# BBB_Breakout_Cape_0.net
KiCad netlist of a schematic drawn in EAGLE
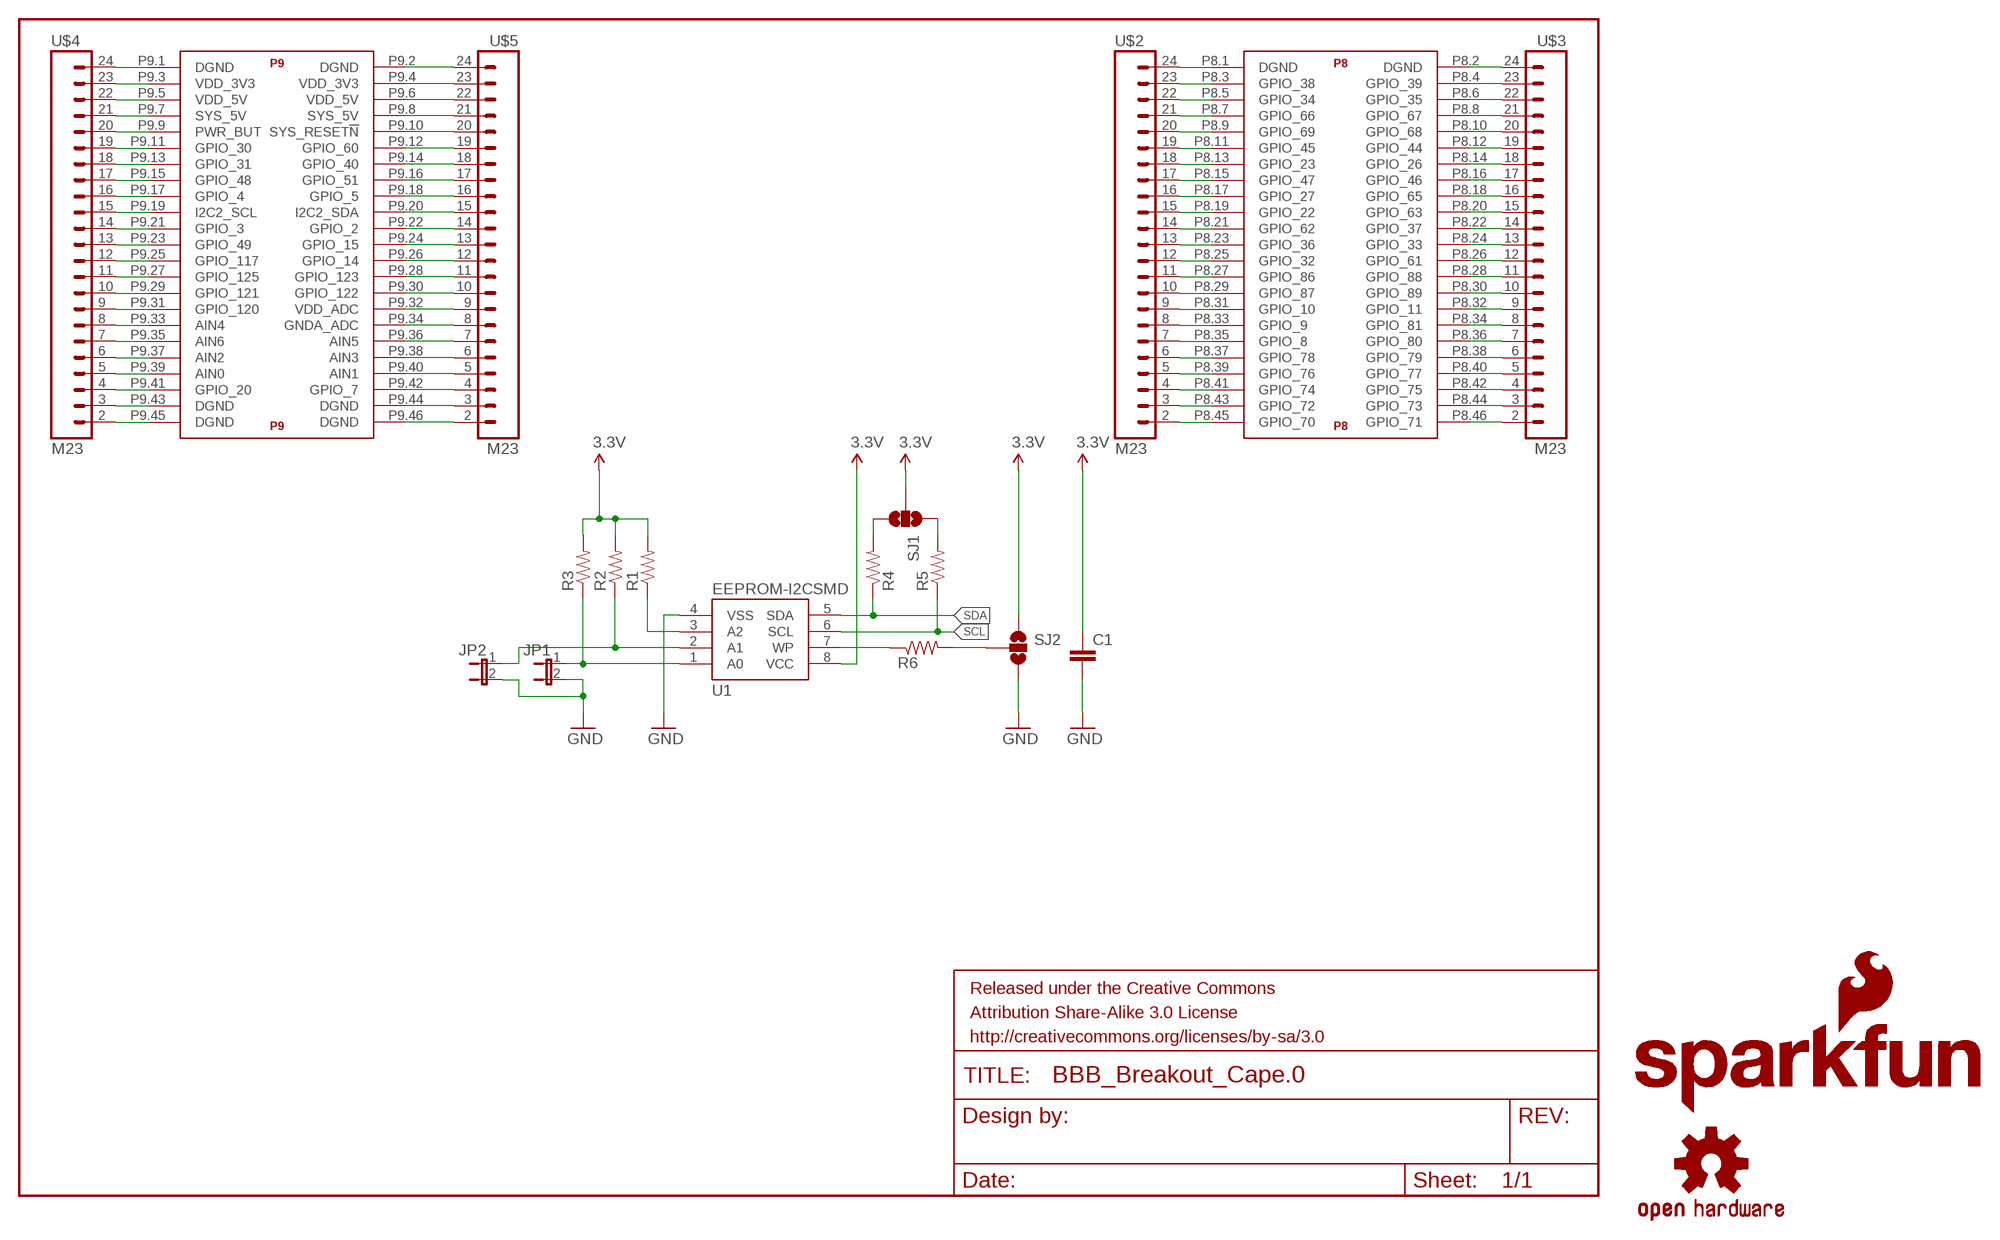
[diagram p0: schematic, sheet 1]

(export (version "E")
  (design (tool "Eeschema 10.0.6"))
  (components
    (comp (ref "C1")
      (value "0.1UF-25V(+80/-20%)(0603)")
      (footprint "eagle-import:0603-CAP")
      (libsource (lib "eagle-import") (part "0.1UF-25V(+80/-20%)(0603)"))
    )
    (comp (ref "FRAME1")
      (value "FRAME-LETTER")
      (footprint "eagle-import:CREATIVE_COMMONS")
      (libsource (lib "eagle-import") (part "FRAME-LETTER"))
    )
    (comp (ref "JP1")
      (value "JUMPER-2SMD-NO")
      (footprint "eagle-import:SJ_2S-NO")
      (libsource (lib "eagle-import") (part "JUMPER-2SMD-NO"))
    )
    (comp (ref "JP2")
      (value "JUMPER-2SMD-NO")
      (footprint "eagle-import:SJ_2S-NO")
      (libsource (lib "eagle-import") (part "JUMPER-2SMD-NO"))
    )
    (comp (ref "LOGO2")
      (value "OSHW-LOGOS")
      (footprint "eagle-import:OSHW-LOGO-S")
      (libsource (lib "eagle-import") (part "OSHW-LOGOS"))
    )
    (comp (ref "LOGO3")
      (value "SFE_LOGO_NAME_FLAME.1_INCH")
      (footprint "eagle-import:SFE_LOGO_NAME_FLAME_.1")
      (libsource (lib "eagle-import") (part "SFE_LOGO_NAME_FLAME.1_INCH"))
    )
    (comp (ref "R1")
      (value "4.7KOHM1/10W1%(0603)")
      (footprint "eagle-import:0603")
      (libsource (lib "eagle-import") (part "4.7KOHM1/10W1%(0603)"))
    )
    (comp (ref "R2")
      (value "4.7KOHM1/10W1%(0603)")
      (footprint "eagle-import:0603")
      (libsource (lib "eagle-import") (part "4.7KOHM1/10W1%(0603)"))
    )
    (comp (ref "R3")
      (value "4.7KOHM1/10W1%(0603)")
      (footprint "eagle-import:0603")
      (libsource (lib "eagle-import") (part "4.7KOHM1/10W1%(0603)"))
    )
    (comp (ref "R4")
      (value "4.7KOHM1/10W1%(0603)")
      (footprint "eagle-import:0603")
      (fields (field (name "PROD_ID") "RES-07857"))
      (libsource (lib "eagle-import") (part "4.7KOHM1/10W1%(0603)"))
    )
    (comp (ref "R5")
      (value "4.7KOHM1/10W1%(0603)")
      (footprint "eagle-import:0603")
      (fields (field (name "PROD_ID") "RES-07857"))
      (libsource (lib "eagle-import") (part "4.7KOHM1/10W1%(0603)"))
    )
    (comp (ref "R6")
      (value "10KOHM1/10W1%(0603)0603")
      (footprint "eagle-import:0603-RES")
      (libsource (lib "eagle-import") (part "10KOHM1/10W1%(0603)0603"))
    )
    (comp (ref "SJ1")
      (value "SOLDERJUMPER_2WAYPASTE1&2&3")
      (footprint "eagle-import:SJ_3_PASTE1&2&3")
      (libsource (lib "eagle-import") (part "SOLDERJUMPER_2WAYPASTE1&2&3"))
    )
    (comp (ref "SJ2")
      (value "SOLDERJUMPER_2WAYPASTE2&3")
      (footprint "eagle-import:SJ_3_PASTE2&3")
      (libsource (lib "eagle-import") (part "SOLDERJUMPER_2WAYPASTE2&3"))
    )
    (comp (ref "U$1")
      (value "BEAGLE_BONE_BLACK_CAPE")
      (footprint "eagle-import:BEAGLE_BONE_BLACK_CAPE")
      (libsource (lib "eagle-import") (part "BEAGLE_BONE_BLACK_CAPE"))
    )
    (comp (ref "U$2")
      (value "M23")
      (footprint "eagle-import:1X23")
      (libsource (lib "eagle-import") (part "M23"))
    )
    (comp (ref "U$3")
      (value "M23")
      (footprint "eagle-import:1X23")
      (libsource (lib "eagle-import") (part "M23"))
    )
    (comp (ref "U$4")
      (value "M23")
      (footprint "eagle-import:1X23")
      (libsource (lib "eagle-import") (part "M23"))
    )
    (comp (ref "U$5")
      (value "M23")
      (footprint "eagle-import:1X23")
      (libsource (lib "eagle-import") (part "M23"))
    )
    (comp (ref "U1")
      (value "EEPROM-I2CSMD")
      (footprint "eagle-import:SO08")
      (libsource (lib "eagle-import") (part "EEPROM-I2CSMD"))
    )
  )
  (nets
    (net (code "1") (name "3.3V") (class "Default")
      (node (ref "C1") (pin "1") (pinfunction "1_1") (pintype "passive"))
      (node (ref "R1") (pin "2") (pinfunction "2_2") (pintype "passive"))
      (node (ref "R2") (pin "2") (pinfunction "2_2") (pintype "passive"))
      (node (ref "R3") (pin "2") (pinfunction "2_2") (pintype "passive"))
      (node (ref "SJ1") (pin "2") (pinfunction "2_2") (pintype "passive"))
      (node (ref "SJ2") (pin "1") (pinfunction "1_1") (pintype "passive"))
      (node (ref "U1") (pin "8") (pinfunction "VCC_8") (pintype "power_in"))
    )
    (net (code "2") (name "GND") (class "Default")
      (node (ref "C1") (pin "2") (pinfunction "2_2") (pintype "passive"))
      (node (ref "JP1") (pin "2") (pinfunction "2_2") (pintype "passive"))
      (node (ref "JP2") (pin "2") (pinfunction "2_2") (pintype "passive"))
      (node (ref "SJ2") (pin "3") (pinfunction "3_3") (pintype "passive"))
      (node (ref "U1") (pin "4") (pinfunction "VSS_4") (pintype "power_in"))
    )
    (net (code "3") (name "Net-(R4-Pad2)") (class "Default")
      (node (ref "R4") (pin "2") (pinfunction "2_2") (pintype "passive"))
      (node (ref "SJ1") (pin "3") (pinfunction "3_3") (pintype "passive"))
    )
    (net (code "4") (name "Net-(R5-Pad2)") (class "Default")
      (node (ref "R5") (pin "2") (pinfunction "2_2") (pintype "passive"))
      (node (ref "SJ1") (pin "1") (pinfunction "1_1") (pintype "passive"))
    )
    (net (code "5") (name "Net-(R6-Pad2)") (class "Default")
      (node (ref "R6") (pin "2") (pinfunction "2_2") (pintype "passive"))
      (node (ref "SJ2") (pin "2") (pinfunction "2_2") (pintype "passive"))
    )
    (net (code "6") (name "Net-(U$1A-DGND-PadP8.1)") (class "Default")
      (node (ref "U$1") (pin "P8.1") (pinfunction "DGND_P8.1") (pintype "bidirectional"))
      (node (ref "U$2") (pin "24") (pinfunction "24_24") (pintype "passive"))
    )
    (net (code "7") (name "Net-(U$1A-DGND-PadP8.2)") (class "Default")
      (node (ref "U$1") (pin "P8.2") (pinfunction "DGND_P8.2") (pintype "bidirectional"))
      (node (ref "U$3") (pin "24") (pinfunction "24_24") (pintype "passive"))
    )
    (net (code "8") (name "Net-(U$1A-GPIO_8)") (class "Default")
      (node (ref "U$1") (pin "P8.35") (pinfunction "GPIO_8_P8.35") (pintype "bidirectional"))
      (node (ref "U$2") (pin "7") (pinfunction "7_7") (pintype "passive"))
    )
    (net (code "9") (name "Net-(U$1A-GPIO_9)") (class "Default")
      (node (ref "U$1") (pin "P8.33") (pinfunction "GPIO_9_P8.33") (pintype "bidirectional"))
      (node (ref "U$2") (pin "8") (pinfunction "8_8") (pintype "passive"))
    )
    (net (code "10") (name "Net-(U$1A-GPIO_10)") (class "Default")
      (node (ref "U$1") (pin "P8.31") (pinfunction "GPIO_10_P8.31") (pintype "bidirectional"))
      (node (ref "U$2") (pin "9") (pinfunction "9_9") (pintype "passive"))
    )
    (net (code "11") (name "Net-(U$1A-GPIO_11)") (class "Default")
      (node (ref "U$1") (pin "P8.32") (pinfunction "GPIO_11_P8.32") (pintype "bidirectional"))
      (node (ref "U$3") (pin "9") (pinfunction "9_9") (pintype "passive"))
    )
    (net (code "12") (name "Net-(U$1A-GPIO_22)") (class "Default")
      (node (ref "U$1") (pin "P8.19") (pinfunction "GPIO_22_P8.19") (pintype "bidirectional"))
      (node (ref "U$2") (pin "15") (pinfunction "15_15") (pintype "passive"))
    )
    (net (code "13") (name "Net-(U$1A-GPIO_23)") (class "Default")
      (node (ref "U$1") (pin "P8.13") (pinfunction "GPIO_23_P8.13") (pintype "bidirectional"))
      (node (ref "U$2") (pin "18") (pinfunction "18_18") (pintype "passive"))
    )
    (net (code "14") (name "Net-(U$1A-GPIO_26)") (class "Default")
      (node (ref "U$1") (pin "P8.14") (pinfunction "GPIO_26_P8.14") (pintype "bidirectional"))
      (node (ref "U$3") (pin "18") (pinfunction "18_18") (pintype "passive"))
    )
    (net (code "15") (name "Net-(U$1A-GPIO_27)") (class "Default")
      (node (ref "U$1") (pin "P8.17") (pinfunction "GPIO_27_P8.17") (pintype "bidirectional"))
      (node (ref "U$2") (pin "16") (pinfunction "16_16") (pintype "passive"))
    )
    (net (code "16") (name "Net-(U$1A-GPIO_32)") (class "Default")
      (node (ref "U$1") (pin "P8.25") (pinfunction "GPIO_32_P8.25") (pintype "bidirectional"))
      (node (ref "U$2") (pin "12") (pinfunction "12_12") (pintype "passive"))
    )
    (net (code "17") (name "Net-(U$1A-GPIO_33)") (class "Default")
      (node (ref "U$1") (pin "P8.24") (pinfunction "GPIO_33_P8.24") (pintype "bidirectional"))
      (node (ref "U$3") (pin "13") (pinfunction "13_13") (pintype "passive"))
    )
    (net (code "18") (name "Net-(U$1A-GPIO_34)") (class "Default")
      (node (ref "U$1") (pin "P8.5") (pinfunction "GPIO_34_P8.5") (pintype "bidirectional"))
      (node (ref "U$2") (pin "22") (pinfunction "22_22") (pintype "passive"))
    )
    (net (code "19") (name "Net-(U$1A-GPIO_35)") (class "Default")
      (node (ref "U$1") (pin "P8.6") (pinfunction "GPIO_35_P8.6") (pintype "bidirectional"))
      (node (ref "U$3") (pin "22") (pinfunction "22_22") (pintype "passive"))
    )
    (net (code "20") (name "Net-(U$1A-GPIO_36)") (class "Default")
      (node (ref "U$1") (pin "P8.23") (pinfunction "GPIO_36_P8.23") (pintype "bidirectional"))
      (node (ref "U$2") (pin "13") (pinfunction "13_13") (pintype "passive"))
    )
    (net (code "21") (name "Net-(U$1A-GPIO_37)") (class "Default")
      (node (ref "U$1") (pin "P8.22") (pinfunction "GPIO_37_P8.22") (pintype "bidirectional"))
      (node (ref "U$3") (pin "14") (pinfunction "14_14") (pintype "passive"))
    )
    (net (code "22") (name "Net-(U$1A-GPIO_38)") (class "Default")
      (node (ref "U$1") (pin "P8.3") (pinfunction "GPIO_38_P8.3") (pintype "bidirectional"))
      (node (ref "U$2") (pin "23") (pinfunction "23_23") (pintype "passive"))
    )
    (net (code "23") (name "Net-(U$1A-GPIO_39)") (class "Default")
      (node (ref "U$1") (pin "P8.4") (pinfunction "GPIO_39_P8.4") (pintype "bidirectional"))
      (node (ref "U$3") (pin "23") (pinfunction "23_23") (pintype "passive"))
    )
    (net (code "24") (name "Net-(U$1A-GPIO_44)") (class "Default")
      (node (ref "U$1") (pin "P8.12") (pinfunction "GPIO_44_P8.12") (pintype "bidirectional"))
      (node (ref "U$3") (pin "19") (pinfunction "19_19") (pintype "passive"))
    )
    (net (code "25") (name "Net-(U$1A-GPIO_45)") (class "Default")
      (node (ref "U$1") (pin "P8.11") (pinfunction "GPIO_45_P8.11") (pintype "bidirectional"))
      (node (ref "U$2") (pin "19") (pinfunction "19_19") (pintype "passive"))
    )
    (net (code "26") (name "Net-(U$1A-GPIO_46)") (class "Default")
      (node (ref "U$1") (pin "P8.16") (pinfunction "GPIO_46_P8.16") (pintype "bidirectional"))
      (node (ref "U$3") (pin "17") (pinfunction "17_17") (pintype "passive"))
    )
    (net (code "27") (name "Net-(U$1A-GPIO_47)") (class "Default")
      (node (ref "U$1") (pin "P8.15") (pinfunction "GPIO_47_P8.15") (pintype "bidirectional"))
      (node (ref "U$2") (pin "17") (pinfunction "17_17") (pintype "passive"))
    )
    (net (code "28") (name "Net-(U$1A-GPIO_61)") (class "Default")
      (node (ref "U$1") (pin "P8.26") (pinfunction "GPIO_61_P8.26") (pintype "bidirectional"))
      (node (ref "U$3") (pin "12") (pinfunction "12_12") (pintype "passive"))
    )
    (net (code "29") (name "Net-(U$1A-GPIO_62)") (class "Default")
      (node (ref "U$1") (pin "P8.21") (pinfunction "GPIO_62_P8.21") (pintype "bidirectional"))
      (node (ref "U$2") (pin "14") (pinfunction "14_14") (pintype "passive"))
    )
    (net (code "30") (name "Net-(U$1A-GPIO_63)") (class "Default")
      (node (ref "U$1") (pin "P8.20") (pinfunction "GPIO_63_P8.20") (pintype "bidirectional"))
      (node (ref "U$3") (pin "15") (pinfunction "15_15") (pintype "passive"))
    )
    (net (code "31") (name "Net-(U$1A-GPIO_65)") (class "Default")
      (node (ref "U$1") (pin "P8.18") (pinfunction "GPIO_65_P8.18") (pintype "bidirectional"))
      (node (ref "U$3") (pin "16") (pinfunction "16_16") (pintype "passive"))
    )
    (net (code "32") (name "Net-(U$1A-GPIO_66)") (class "Default")
      (node (ref "U$1") (pin "P8.7") (pinfunction "GPIO_66_P8.7") (pintype "bidirectional"))
      (node (ref "U$2") (pin "21") (pinfunction "21_21") (pintype "passive"))
    )
    (net (code "33") (name "Net-(U$1A-GPIO_67)") (class "Default")
      (node (ref "U$1") (pin "P8.8") (pinfunction "GPIO_67_P8.8") (pintype "bidirectional"))
      (node (ref "U$3") (pin "21") (pinfunction "21_21") (pintype "passive"))
    )
    (net (code "34") (name "Net-(U$1A-GPIO_68)") (class "Default")
      (node (ref "U$1") (pin "P8.10") (pinfunction "GPIO_68_P8.10") (pintype "bidirectional"))
      (node (ref "U$3") (pin "20") (pinfunction "20_20") (pintype "passive"))
    )
    (net (code "35") (name "Net-(U$1A-GPIO_69)") (class "Default")
      (node (ref "U$1") (pin "P8.9") (pinfunction "GPIO_69_P8.9") (pintype "bidirectional"))
      (node (ref "U$2") (pin "20") (pinfunction "20_20") (pintype "passive"))
    )
    (net (code "36") (name "Net-(U$1A-GPIO_70)") (class "Default")
      (node (ref "U$1") (pin "P8.45") (pinfunction "GPIO_70_P8.45") (pintype "bidirectional"))
      (node (ref "U$2") (pin "2") (pinfunction "2_2") (pintype "passive"))
    )
    (net (code "37") (name "Net-(U$1A-GPIO_71)") (class "Default")
      (node (ref "U$1") (pin "P8.46") (pinfunction "GPIO_71_P8.46") (pintype "bidirectional"))
      (node (ref "U$3") (pin "2") (pinfunction "2_2") (pintype "passive"))
    )
    (net (code "38") (name "Net-(U$1A-GPIO_72)") (class "Default")
      (node (ref "U$1") (pin "P8.43") (pinfunction "GPIO_72_P8.43") (pintype "bidirectional"))
      (node (ref "U$2") (pin "3") (pinfunction "3_3") (pintype "passive"))
    )
    (net (code "39") (name "Net-(U$1A-GPIO_73)") (class "Default")
      (node (ref "U$1") (pin "P8.44") (pinfunction "GPIO_73_P8.44") (pintype "bidirectional"))
      (node (ref "U$3") (pin "3") (pinfunction "3_3") (pintype "passive"))
    )
    (net (code "40") (name "Net-(U$1A-GPIO_74)") (class "Default")
      (node (ref "U$1") (pin "P8.41") (pinfunction "GPIO_74_P8.41") (pintype "bidirectional"))
      (node (ref "U$2") (pin "4") (pinfunction "4_4") (pintype "passive"))
    )
    (net (code "41") (name "Net-(U$1A-GPIO_75)") (class "Default")
      (node (ref "U$1") (pin "P8.42") (pinfunction "GPIO_75_P8.42") (pintype "bidirectional"))
      (node (ref "U$3") (pin "4") (pinfunction "4_4") (pintype "passive"))
    )
    (net (code "42") (name "Net-(U$1A-GPIO_76)") (class "Default")
      (node (ref "U$1") (pin "P8.39") (pinfunction "GPIO_76_P8.39") (pintype "bidirectional"))
      (node (ref "U$2") (pin "5") (pinfunction "5_5") (pintype "passive"))
    )
    (net (code "43") (name "Net-(U$1A-GPIO_77)") (class "Default")
      (node (ref "U$1") (pin "P8.40") (pinfunction "GPIO_77_P8.40") (pintype "bidirectional"))
      (node (ref "U$3") (pin "5") (pinfunction "5_5") (pintype "passive"))
    )
    (net (code "44") (name "Net-(U$1A-GPIO_78)") (class "Default")
      (node (ref "U$1") (pin "P8.37") (pinfunction "GPIO_78_P8.37") (pintype "bidirectional"))
      (node (ref "U$2") (pin "6") (pinfunction "6_6") (pintype "passive"))
    )
    (net (code "45") (name "Net-(U$1A-GPIO_79)") (class "Default")
      (node (ref "U$1") (pin "P8.38") (pinfunction "GPIO_79_P8.38") (pintype "bidirectional"))
      (node (ref "U$3") (pin "6") (pinfunction "6_6") (pintype "passive"))
    )
    (net (code "46") (name "Net-(U$1A-GPIO_80)") (class "Default")
      (node (ref "U$1") (pin "P8.36") (pinfunction "GPIO_80_P8.36") (pintype "bidirectional"))
      (node (ref "U$3") (pin "7") (pinfunction "7_7") (pintype "passive"))
    )
    (net (code "47") (name "Net-(U$1A-GPIO_81)") (class "Default")
      (node (ref "U$1") (pin "P8.34") (pinfunction "GPIO_81_P8.34") (pintype "bidirectional"))
      (node (ref "U$3") (pin "8") (pinfunction "8_8") (pintype "passive"))
    )
    (net (code "48") (name "Net-(U$1A-GPIO_86)") (class "Default")
      (node (ref "U$1") (pin "P8.27") (pinfunction "GPIO_86_P8.27") (pintype "bidirectional"))
      (node (ref "U$2") (pin "11") (pinfunction "11_11") (pintype "passive"))
    )
    (net (code "49") (name "Net-(U$1A-GPIO_87)") (class "Default")
      (node (ref "U$1") (pin "P8.29") (pinfunction "GPIO_87_P8.29") (pintype "bidirectional"))
      (node (ref "U$2") (pin "10") (pinfunction "10_10") (pintype "passive"))
    )
    (net (code "50") (name "Net-(U$1A-GPIO_88)") (class "Default")
      (node (ref "U$1") (pin "P8.28") (pinfunction "GPIO_88_P8.28") (pintype "bidirectional"))
      (node (ref "U$3") (pin "11") (pinfunction "11_11") (pintype "passive"))
    )
    (net (code "51") (name "Net-(U$1A-GPIO_89)") (class "Default")
      (node (ref "U$1") (pin "P8.30") (pinfunction "GPIO_89_P8.30") (pintype "bidirectional"))
      (node (ref "U$3") (pin "10") (pinfunction "10_10") (pintype "passive"))
    )
    (net (code "52") (name "Net-(U$1B-AIN0)") (class "Default")
      (node (ref "U$1") (pin "P9.39") (pinfunction "AIN0_P9.39") (pintype "bidirectional"))
      (node (ref "U$4") (pin "5") (pinfunction "5_5") (pintype "passive"))
    )
    (net (code "53") (name "Net-(U$1B-AIN1)") (class "Default")
      (node (ref "U$1") (pin "P9.40") (pinfunction "AIN1_P9.40") (pintype "bidirectional"))
      (node (ref "U$5") (pin "5") (pinfunction "5_5") (pintype "passive"))
    )
    (net (code "54") (name "Net-(U$1B-AIN2)") (class "Default")
      (node (ref "U$1") (pin "P9.37") (pinfunction "AIN2_P9.37") (pintype "bidirectional"))
      (node (ref "U$4") (pin "6") (pinfunction "6_6") (pintype "passive"))
    )
    (net (code "55") (name "Net-(U$1B-AIN3)") (class "Default")
      (node (ref "U$1") (pin "P9.38") (pinfunction "AIN3_P9.38") (pintype "bidirectional"))
      (node (ref "U$5") (pin "6") (pinfunction "6_6") (pintype "passive"))
    )
    (net (code "56") (name "Net-(U$1B-AIN4)") (class "Default")
      (node (ref "U$1") (pin "P9.33") (pinfunction "AIN4_P9.33") (pintype "bidirectional"))
      (node (ref "U$4") (pin "8") (pinfunction "8_8") (pintype "passive"))
    )
    (net (code "57") (name "Net-(U$1B-AIN5)") (class "Default")
      (node (ref "U$1") (pin "P9.36") (pinfunction "AIN5_P9.36") (pintype "bidirectional"))
      (node (ref "U$5") (pin "7") (pinfunction "7_7") (pintype "passive"))
    )
    (net (code "58") (name "Net-(U$1B-AIN6)") (class "Default")
      (node (ref "U$1") (pin "P9.35") (pinfunction "AIN6_P9.35") (pintype "bidirectional"))
      (node (ref "U$4") (pin "7") (pinfunction "7_7") (pintype "passive"))
    )
    (net (code "59") (name "Net-(U$1B-DGND-PadP9.1)") (class "Default")
      (node (ref "U$1") (pin "P9.1") (pinfunction "DGND_P9.1") (pintype "bidirectional"))
      (node (ref "U$4") (pin "24") (pinfunction "24_24") (pintype "passive"))
    )
    (net (code "60") (name "Net-(U$1B-DGND-PadP9.2)") (class "Default")
      (node (ref "U$1") (pin "P9.2") (pinfunction "DGND_P9.2") (pintype "bidirectional"))
      (node (ref "U$5") (pin "24") (pinfunction "24_24") (pintype "passive"))
    )
    (net (code "61") (name "Net-(U$1B-DGND-PadP9.43)") (class "Default")
      (node (ref "U$1") (pin "P9.43") (pinfunction "DGND_P9.43") (pintype "bidirectional"))
      (node (ref "U$4") (pin "3") (pinfunction "3_3") (pintype "passive"))
    )
    (net (code "62") (name "Net-(U$1B-DGND-PadP9.44)") (class "Default")
      (node (ref "U$1") (pin "P9.44") (pinfunction "DGND_P9.44") (pintype "bidirectional"))
      (node (ref "U$5") (pin "3") (pinfunction "3_3") (pintype "passive"))
    )
    (net (code "63") (name "Net-(U$1B-DGND-PadP9.45)") (class "Default")
      (node (ref "U$1") (pin "P9.45") (pinfunction "DGND_P9.45") (pintype "bidirectional"))
      (node (ref "U$4") (pin "2") (pinfunction "2_2") (pintype "passive"))
    )
    (net (code "64") (name "Net-(U$1B-DGND-PadP9.46)") (class "Default")
      (node (ref "U$1") (pin "P9.46") (pinfunction "DGND_P9.46") (pintype "bidirectional"))
      (node (ref "U$5") (pin "2") (pinfunction "2_2") (pintype "passive"))
    )
    (net (code "65") (name "Net-(U$1B-GNDA_ADC)") (class "Default")
      (node (ref "U$1") (pin "P9.34") (pinfunction "GNDA_ADC_P9.34") (pintype "bidirectional"))
      (node (ref "U$5") (pin "8") (pinfunction "8_8") (pintype "passive"))
    )
    (net (code "66") (name "Net-(U$1B-GPIO_2)") (class "Default")
      (node (ref "U$1") (pin "P9.22") (pinfunction "GPIO_2_P9.22") (pintype "bidirectional"))
      (node (ref "U$5") (pin "14") (pinfunction "14_14") (pintype "passive"))
    )
    (net (code "67") (name "Net-(U$1B-GPIO_3)") (class "Default")
      (node (ref "U$1") (pin "P9.21") (pinfunction "GPIO_3_P9.21") (pintype "bidirectional"))
      (node (ref "U$4") (pin "14") (pinfunction "14_14") (pintype "passive"))
    )
    (net (code "68") (name "Net-(U$1B-GPIO_4)") (class "Default")
      (node (ref "U$1") (pin "P9.17") (pinfunction "GPIO_4_P9.17") (pintype "bidirectional"))
      (node (ref "U$4") (pin "16") (pinfunction "16_16") (pintype "passive"))
    )
    (net (code "69") (name "Net-(U$1B-GPIO_5)") (class "Default")
      (node (ref "U$1") (pin "P9.18") (pinfunction "GPIO_5_P9.18") (pintype "bidirectional"))
      (node (ref "U$5") (pin "16") (pinfunction "16_16") (pintype "passive"))
    )
    (net (code "70") (name "Net-(U$1B-GPIO_7)") (class "Default")
      (node (ref "U$1") (pin "P9.42") (pinfunction "GPIO_7_P9.42") (pintype "bidirectional"))
      (node (ref "U$5") (pin "4") (pinfunction "4_4") (pintype "passive"))
    )
    (net (code "71") (name "Net-(U$1B-GPIO_14)") (class "Default")
      (node (ref "U$1") (pin "P9.26") (pinfunction "GPIO_14_P9.26") (pintype "bidirectional"))
      (node (ref "U$5") (pin "12") (pinfunction "12_12") (pintype "passive"))
    )
    (net (code "72") (name "Net-(U$1B-GPIO_15)") (class "Default")
      (node (ref "U$1") (pin "P9.24") (pinfunction "GPIO_15_P9.24") (pintype "bidirectional"))
      (node (ref "U$5") (pin "13") (pinfunction "13_13") (pintype "passive"))
    )
    (net (code "73") (name "Net-(U$1B-GPIO_20)") (class "Default")
      (node (ref "U$1") (pin "P9.41") (pinfunction "GPIO_20_P9.41") (pintype "bidirectional"))
      (node (ref "U$4") (pin "4") (pinfunction "4_4") (pintype "passive"))
    )
    (net (code "74") (name "Net-(U$1B-GPIO_30)") (class "Default")
      (node (ref "U$1") (pin "P9.11") (pinfunction "GPIO_30_P9.11") (pintype "bidirectional"))
      (node (ref "U$4") (pin "19") (pinfunction "19_19") (pintype "passive"))
    )
    (net (code "75") (name "Net-(U$1B-GPIO_31)") (class "Default")
      (node (ref "U$1") (pin "P9.13") (pinfunction "GPIO_31_P9.13") (pintype "bidirectional"))
      (node (ref "U$4") (pin "18") (pinfunction "18_18") (pintype "passive"))
    )
    (net (code "76") (name "Net-(U$1B-GPIO_40)") (class "Default")
      (node (ref "U$1") (pin "P9.14") (pinfunction "GPIO_40_P9.14") (pintype "bidirectional"))
      (node (ref "U$5") (pin "18") (pinfunction "18_18") (pintype "passive"))
    )
    (net (code "77") (name "Net-(U$1B-GPIO_48)") (class "Default")
      (node (ref "U$1") (pin "P9.15") (pinfunction "GPIO_48_P9.15") (pintype "bidirectional"))
      (node (ref "U$4") (pin "17") (pinfunction "17_17") (pintype "passive"))
    )
    (net (code "78") (name "Net-(U$1B-GPIO_49)") (class "Default")
      (node (ref "U$1") (pin "P9.23") (pinfunction "GPIO_49_P9.23") (pintype "bidirectional"))
      (node (ref "U$4") (pin "13") (pinfunction "13_13") (pintype "passive"))
    )
    (net (code "79") (name "Net-(U$1B-GPIO_51)") (class "Default")
      (node (ref "U$1") (pin "P9.16") (pinfunction "GPIO_51_P9.16") (pintype "bidirectional"))
      (node (ref "U$5") (pin "17") (pinfunction "17_17") (pintype "passive"))
    )
    (net (code "80") (name "Net-(U$1B-GPIO_60)") (class "Default")
      (node (ref "U$1") (pin "P9.12") (pinfunction "GPIO_60_P9.12") (pintype "bidirectional"))
      (node (ref "U$5") (pin "19") (pinfunction "19_19") (pintype "passive"))
    )
    (net (code "81") (name "Net-(U$1B-GPIO_117)") (class "Default")
      (node (ref "U$1") (pin "P9.25") (pinfunction "GPIO_117_P9.25") (pintype "bidirectional"))
      (node (ref "U$4") (pin "12") (pinfunction "12_12") (pintype "passive"))
    )
    (net (code "82") (name "Net-(U$1B-GPIO_120)") (class "Default")
      (node (ref "U$1") (pin "P9.31") (pinfunction "GPIO_120_P9.31") (pintype "bidirectional"))
      (node (ref "U$4") (pin "9") (pinfunction "9_9") (pintype "passive"))
    )
    (net (code "83") (name "Net-(U$1B-GPIO_121)") (class "Default")
      (node (ref "U$1") (pin "P9.29") (pinfunction "GPIO_121_P9.29") (pintype "bidirectional"))
      (node (ref "U$4") (pin "10") (pinfunction "10_10") (pintype "passive"))
    )
    (net (code "84") (name "Net-(U$1B-GPIO_122)") (class "Default")
      (node (ref "U$1") (pin "P9.30") (pinfunction "GPIO_122_P9.30") (pintype "bidirectional"))
      (node (ref "U$5") (pin "10") (pinfunction "10_10") (pintype "passive"))
    )
    (net (code "85") (name "Net-(U$1B-GPIO_123)") (class "Default")
      (node (ref "U$1") (pin "P9.28") (pinfunction "GPIO_123_P9.28") (pintype "bidirectional"))
      (node (ref "U$5") (pin "11") (pinfunction "11_11") (pintype "passive"))
    )
    (net (code "86") (name "Net-(U$1B-GPIO_125)") (class "Default")
      (node (ref "U$1") (pin "P9.27") (pinfunction "GPIO_125_P9.27") (pintype "bidirectional"))
      (node (ref "U$4") (pin "11") (pinfunction "11_11") (pintype "passive"))
    )
    (net (code "87") (name "Net-(U$1B-I2C2_SCL)") (class "Default")
      (node (ref "U$1") (pin "P9.19") (pinfunction "I2C2_SCL_P9.19") (pintype "bidirectional"))
      (node (ref "U$4") (pin "15") (pinfunction "15_15") (pintype "passive"))
    )
    (net (code "88") (name "Net-(U$1B-I2C2_SDA)") (class "Default")
      (node (ref "U$1") (pin "P9.20") (pinfunction "I2C2_SDA_P9.20") (pintype "bidirectional"))
      (node (ref "U$5") (pin "15") (pinfunction "15_15") (pintype "passive"))
    )
    (net (code "89") (name "Net-(U$1B-PWR_BUT)") (class "Default")
      (node (ref "U$1") (pin "P9.9") (pinfunction "PWR_BUT_P9.9") (pintype "bidirectional"))
      (node (ref "U$4") (pin "20") (pinfunction "20_20") (pintype "passive"))
    )
    (net (code "90") (name "Net-(U$1B-SYS_5V-PadP9.7)") (class "Default")
      (node (ref "U$1") (pin "P9.7") (pinfunction "SYS_5V_P9.7") (pintype "bidirectional"))
      (node (ref "U$4") (pin "21") (pinfunction "21_21") (pintype "passive"))
    )
    (net (code "91") (name "Net-(U$1B-SYS_5V-PadP9.8)") (class "Default")
      (node (ref "U$1") (pin "P9.8") (pinfunction "SYS_5V_P9.8") (pintype "bidirectional"))
      (node (ref "U$5") (pin "21") (pinfunction "21_21") (pintype "passive"))
    )
    (net (code "92") (name "Net-(U$1B-SYS_RESET~{N})") (class "Default")
      (node (ref "U$1") (pin "P9.10") (pinfunction "SYS_RESET~{N}_P9.10") (pintype "bidirectional"))
      (node (ref "U$5") (pin "20") (pinfunction "20_20") (pintype "passive"))
    )
    (net (code "93") (name "Net-(U$1B-VDD_3V3-PadP9.3)") (class "Default")
      (node (ref "U$1") (pin "P9.3") (pinfunction "VDD_3V3_P9.3") (pintype "bidirectional"))
      (node (ref "U$4") (pin "23") (pinfunction "23_23") (pintype "passive"))
    )
    (net (code "94") (name "Net-(U$1B-VDD_3V3-PadP9.4)") (class "Default")
      (node (ref "U$1") (pin "P9.4") (pinfunction "VDD_3V3_P9.4") (pintype "bidirectional"))
      (node (ref "U$5") (pin "23") (pinfunction "23_23") (pintype "passive"))
    )
    (net (code "95") (name "Net-(U$1B-VDD_5V-PadP9.5)") (class "Default")
      (node (ref "U$1") (pin "P9.5") (pinfunction "VDD_5V_P9.5") (pintype "bidirectional"))
      (node (ref "U$4") (pin "22") (pinfunction "22_22") (pintype "passive"))
    )
    (net (code "96") (name "Net-(U$1B-VDD_5V-PadP9.6)") (class "Default")
      (node (ref "U$1") (pin "P9.6") (pinfunction "VDD_5V_P9.6") (pintype "bidirectional"))
      (node (ref "U$5") (pin "22") (pinfunction "22_22") (pintype "passive"))
    )
    (net (code "97") (name "Net-(U$1B-VDD_ADC)") (class "Default")
      (node (ref "U$1") (pin "P9.32") (pinfunction "VDD_ADC_P9.32") (pintype "bidirectional"))
      (node (ref "U$5") (pin "9") (pinfunction "9_9") (pintype "passive"))
    )
    (net (code "98") (name "Net-(U1-A0)") (class "Default")
      (node (ref "JP1") (pin "1") (pinfunction "1_1") (pintype "passive"))
      (node (ref "R3") (pin "1") (pinfunction "1_1") (pintype "passive"))
      (node (ref "U1") (pin "1") (pinfunction "A0_1") (pintype "bidirectional"))
    )
    (net (code "99") (name "Net-(U1-A1)") (class "Default")
      (node (ref "JP2") (pin "1") (pinfunction "1_1") (pintype "passive"))
      (node (ref "R2") (pin "1") (pinfunction "1_1") (pintype "passive"))
      (node (ref "U1") (pin "2") (pinfunction "A1_2") (pintype "bidirectional"))
    )
    (net (code "100") (name "Net-(U1-A2)") (class "Default")
      (node (ref "R1") (pin "1") (pinfunction "1_1") (pintype "passive"))
      (node (ref "U1") (pin "3") (pinfunction "A2_3") (pintype "bidirectional"))
    )
    (net (code "101") (name "Net-(U1-WP)") (class "Default")
      (node (ref "R6") (pin "1") (pinfunction "1_1") (pintype "passive"))
      (node (ref "U1") (pin "7") (pinfunction "WP_7") (pintype "bidirectional"))
    )
    (net (code "102") (name "SCL") (class "Default")
      (node (ref "R5") (pin "1") (pinfunction "1_1") (pintype "passive"))
      (node (ref "U1") (pin "6") (pinfunction "SCL_6") (pintype "bidirectional"))
    )
    (net (code "103") (name "SDA") (class "Default")
      (node (ref "R4") (pin "1") (pinfunction "1_1") (pintype "passive"))
      (node (ref "U1") (pin "5") (pinfunction "SDA_5") (pintype "bidirectional"))
    )
  )
)
